# CAN_Interface.net
KiCad netlist of a schematic drawn in Altium Designer
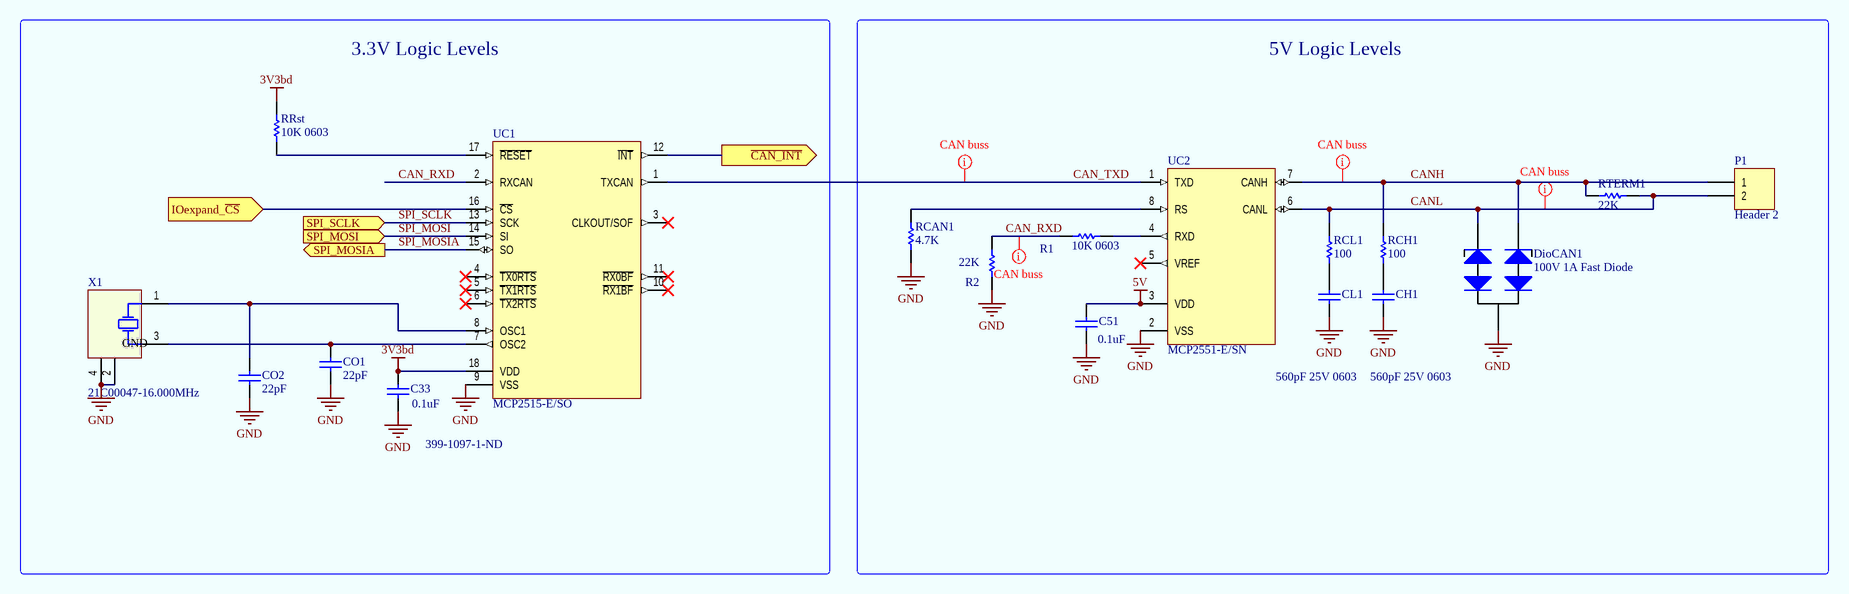
[diagram p0: CAN_Interface.SchDoc]

(export (version "E")
  (design (tool "Eeschema 10.0.6"))
  (components
    (comp (ref "C33")
      (value "0.1uF")
      (footprint "0603C_L")
      (fields
        (field (name "SUPPLIER PART NUMBER 1") "399-1097-1-ND")
        (field (name "MANUFACTURER") "Kemet")
        (field (name "MANUFACTURER PART NUMBER") "C0603C104J4RACTU")
        (field (name "TOLERANCE") "5%")
      )
      (libsource (lib "WCT") (part "Cap10uF_25V_0603"))
    )
    (comp (ref "C51")
      (value "0.1uF")
      (footprint "0603C_L")
      (libsource (lib "ICEdigikey") (part "Cap10uF_25V_0603"))
    )
    (comp (ref "CH1")
      (value "560pF 25V 0603")
      (footprint "0603C_L")
      (fields
        (field (name "MANUFACTURER") "Taiyo Yuden")
        (field (name "MANUFACTURER PART NUMBER") "TMK316F106ZL-T")
        (field (name "TOLERANCE") "-20%, +80%")
      )
      (libsource (lib "WCT") (part "Cap560pF_25V_0603"))
    )
    (comp (ref "CL1")
      (value "560pF 25V 0603")
      (footprint "0603C_L")
      (fields
        (field (name "MANUFACTURER") "Taiyo Yuden")
        (field (name "MANUFACTURER PART NUMBER") "TMK316F106ZL-T")
        (field (name "TOLERANCE") "-20%, +80%")
      )
      (libsource (lib "WCT") (part "Cap560pF_25V_0603"))
    )
    (comp (ref "CO1")
      (value "22pF")
      (footprint "0603C_L")
      (fields
        (field (name "MANUFACTURER") "Murata")
        (field (name "MANUFACTURER PART NUMBER") "GRM1885C1H220JA01D")
        (field (name "TOLERANCE") "5")
      )
      (libsource (lib "WCT") (part "Cap22pF_50V_0603"))
    )
    (comp (ref "CO2")
      (value "22pF")
      (footprint "0603C_L")
      (fields
        (field (name "MANUFACTURER") "Murata")
        (field (name "MANUFACTURER PART NUMBER") "GRM1885C1H220JA01D")
        (field (name "TOLERANCE") "5")
      )
      (libsource (lib "WCT") (part "Cap101nF_50V_0603"))
    )
    (comp (ref "DioCAN1")
      (value "100V 1A Fast Diode")
      (footprint "SOT23")
      (description "High Conductance Fast Diode")
      (fields
        (field (name "MANUFACTURER") "ON Semiconductor")
        (field (name "MANUFACTURER PART NUMBER") "MUR110RLG")
      )
      (libsource (lib "WCT") (part "PESD1CAN"))
    )
    (comp (ref "P1")
      (value "Header 2")
      (footprint "HDR1X2")
      (description "Header, 2-Pin")
      (fields (field (name "PUBLISHER") "Altium Limited"))
      (libsource (lib "Miscellaneous Connectors") (part "Header 2"))
    )
    (comp (ref "R1")
      (value "10K 0603")
      (footprint "0603_L")
      (fields
        (field (name "MANUFACTURER") "Yageo")
        (field (name "MANUFACTURER PART NUMBER") "RT0603DRD074K99L")
        (field (name "TOLERANCE") "±0.5%")
      )
      (libsource (lib "ICEdigikey") (part "Res4K99_0603"))
    )
    (comp (ref "R2")
      (value "22K")
      (footprint "0603_L")
      (fields
        (field (name "MANUFACTURER") "Yageo")
        (field (name "MANUFACTURER PART NUMBER") "RT0603DRD0722KL")
        (field (name "TOLERANCE") "0.5 %")
      )
      (libsource (lib "ICEdigikey") (part "Res_0603"))
    )
    (comp (ref "RCAN1")
      (value "4.7K")
      (footprint "0603_L")
      (fields
        (field (name "MANUFACTURER") "Yageo")
        (field (name "MANUFACTURER PART NUMBER") "RT0603DRD074K99L")
        (field (name "TOLERANCE") "±0.5%")
      )
      (libsource (lib "ICEdigikey") (part "Res4K99_0603"))
    )
    (comp (ref "RCH1")
      (value "100")
      (footprint "0603_L")
      (fields
        (field (name "MANUFACTURER") "Yageo")
        (field (name "MANUFACTURER PART NUMBER") "RC0603JR-07330RL")
        (field (name "TOLERANCE") "±5%")
      )
      (libsource (lib "ICEdigikey") (part "Res330_0603"))
    )
    (comp (ref "RCL1")
      (value "100")
      (footprint "0603_L")
      (fields
        (field (name "MANUFACTURER") "Yageo")
        (field (name "MANUFACTURER PART NUMBER") "RC0603JR-07330RL")
        (field (name "TOLERANCE") "±5%")
      )
      (libsource (lib "ICEdigikey") (part "Res330_0603"))
    )
    (comp (ref "RRst")
      (value "10K 0603")
      (footprint "0603_L")
      (fields
        (field (name "MANUFACTURER") "Panasonic Electronic Components")
        (field (name "MANUFACTURER PART NUMBER") "ERJ-3GEYJ102V")
        (field (name "TOLERANCE") "±5%")
      )
      (libsource (lib "WCT") (part "Res10K_0603"))
    )
    (comp (ref "RTERM1")
      (value "22K")
      (footprint "0603_L")
      (fields
        (field (name "MANUFACTURER") "Yageo")
        (field (name "MANUFACTURER PART NUMBER") "RT0603DRD0722KL")
        (field (name "TOLERANCE") "0.5 %")
      )
      (libsource (lib "WCT") (part "Res_0603"))
    )
    (comp (ref "UC1")
      (value "MCP2515-E/SO")
      (footprint "SOIC-SO18_M")
      (description "Stand-Alone CAN Controller With SPI Interface, 18-Pin SOIC, Extended Temperature")
      (libsource (lib "Altium Content Vault") (part "CMP-0186-00035-2"))
    )
    (comp (ref "UC2")
      (value "MCP2551-E/SN")
      (footprint "SOIC-SN8_N")
      (description "High-Speed CAN Transceiver, 8-Pin SOIC, Extended Temperature")
      (libsource (lib "Altium Content Vault") (part "CMP-0186-00038-2"))
    )
    (comp (ref "X1")
      (value "21C00047-16.000MHz")
      (footprint "ITTI-21C00047-16.000MHz-4_V")
      (description "Crystal, 16 MHz, -30 to 85 degC, 3.2 x 2.5 x 0.9 mm SMD")
      (fields (field (name "MANUFACTURER") "ITTI"))
      (libsource (lib "Altium Content Vault") (part "CMP-0464-00001-2"))
    )
  )
  (nets
    (net (code "1") (name "/CANH") (class "Default")
      (node (ref "DioCAN1") (pin "1") (pinfunction "A_1") (pintype "passive"))
      (node (ref "P1") (pin "1") (pinfunction "1_1") (pintype "passive"))
      (node (ref "RCH1") (pin "2") (pinfunction "2_2") (pintype "passive"))
      (node (ref "RTERM1") (pin "2") (pinfunction "2_2") (pintype "passive"))
      (node (ref "UC2") (pin "7") (pinfunction "CANH_7") (pintype "bidirectional"))
    )
    (net (code "2") (name "/CANL") (class "Default")
      (node (ref "DioCAN1") (pin "2") (pinfunction "K_2") (pintype "passive"))
      (node (ref "P1") (pin "2") (pinfunction "2_2") (pintype "passive"))
      (node (ref "RCL1") (pin "2") (pinfunction "2_2") (pintype "passive"))
      (node (ref "RTERM1") (pin "1") (pinfunction "1_1") (pintype "passive"))
      (node (ref "UC2") (pin "6") (pinfunction "CANL_6") (pintype "bidirectional"))
    )
    (net (code "3") (name "/CAN_INT") (class "Default")
      (node (ref "UC1") (pin "12") (pinfunction "~{INT}_12") (pintype "output"))
    )
    (net (code "4") (name "/CAN_RXD") (class "Default")
      (node (ref "R1") (pin "2") (pinfunction "2_2") (pintype "passive"))
      (node (ref "R2") (pin "2") (pinfunction "2_2") (pintype "passive"))
      (node (ref "UC1") (pin "2") (pinfunction "RXCAN_2") (pintype "input"))
    )
    (net (code "5") (name "/CAN_TXD") (class "Default")
      (node (ref "UC1") (pin "1") (pinfunction "TXCAN_1") (pintype "output"))
      (node (ref "UC2") (pin "1") (pinfunction "TXD_1") (pintype "input"))
    )
    (net (code "6") (name "/IOexpand_~{CS}") (class "Default")
      (node (ref "UC1") (pin "16") (pinfunction "~{CS}_16") (pintype "input"))
    )
    (net (code "7") (name "/SPI_MOSI") (class "Default")
      (node (ref "UC1") (pin "14") (pinfunction "SI_14") (pintype "input"))
    )
    (net (code "8") (name "/SPI_MOSIA") (class "Default")
      (node (ref "UC1") (pin "15") (pinfunction "SO_15") (pintype "bidirectional"))
    )
    (net (code "9") (name "/SPI_SCLK") (class "Default")
      (node (ref "UC1") (pin "13") (pinfunction "SCK_13") (pintype "input"))
    )
    (net (code "10") (name "3V3bd") (class "Default")
      (node (ref "C33") (pin "2") (pinfunction "2_2") (pintype "passive"))
      (node (ref "RRst") (pin "2") (pinfunction "2_2") (pintype "passive"))
      (node (ref "UC1") (pin "18") (pinfunction "VDD_18") (pintype "power_in"))
    )
    (net (code "11") (name "5V") (class "Default")
      (node (ref "C51") (pin "2") (pinfunction "2_2") (pintype "passive"))
      (node (ref "UC2") (pin "3") (pinfunction "VDD_3") (pintype "power_in"))
    )
    (net (code "12") (name "GND") (class "Default")
      (node (ref "C33") (pin "1") (pinfunction "1_1") (pintype "passive"))
      (node (ref "C51") (pin "1") (pinfunction "1_1") (pintype "passive"))
      (node (ref "CH1") (pin "2") (pinfunction "2_2") (pintype "passive"))
      (node (ref "CL1") (pin "1") (pinfunction "1_1") (pintype "passive"))
      (node (ref "CO1") (pin "1") (pinfunction "1_1") (pintype "passive"))
      (node (ref "CO2") (pin "2") (pinfunction "2_2") (pintype "passive"))
      (node (ref "DioCAN1") (pin "3") (pinfunction "3_3") (pintype "passive"))
      (node (ref "R2") (pin "1") (pinfunction "1_1") (pintype "passive"))
      (node (ref "RCAN1") (pin "1") (pinfunction "1_1") (pintype "passive"))
      (node (ref "UC1") (pin "9") (pinfunction "VSS_9") (pintype "power_in"))
      (node (ref "UC2") (pin "2") (pinfunction "VSS_2") (pintype "power_in"))
      (node (ref "X1") (pin "2") (pinfunction "GND_2") (pintype "power_in"))
      (node (ref "X1") (pin "4") (pinfunction "GND_4") (pintype "power_in"))
    )
    (net (code "13") (name "Net-(CH1-Pad1)") (class "Default")
      (node (ref "CH1") (pin "1") (pinfunction "1_1") (pintype "passive"))
      (node (ref "RCH1") (pin "1") (pinfunction "1_1") (pintype "passive"))
    )
    (net (code "14") (name "Net-(CL1-Pad2)") (class "Default")
      (node (ref "CL1") (pin "2") (pinfunction "2_2") (pintype "passive"))
      (node (ref "RCL1") (pin "1") (pinfunction "1_1") (pintype "passive"))
    )
    (net (code "15") (name "Net-(UC1-OSC1)") (class "Default")
      (node (ref "CO2") (pin "1") (pinfunction "1_1") (pintype "passive"))
      (node (ref "UC1") (pin "8") (pinfunction "OSC1_8") (pintype "input"))
      (node (ref "X1") (pin "1") (pinfunction "XTAL_1") (pintype "passive"))
    )
    (net (code "16") (name "Net-(UC1-OSC2)") (class "Default")
      (node (ref "CO1") (pin "2") (pinfunction "2_2") (pintype "passive"))
      (node (ref "UC1") (pin "7") (pinfunction "OSC2_7") (pintype "output"))
      (node (ref "X1") (pin "3") (pinfunction "XTAL_3") (pintype "passive"))
    )
    (net (code "17") (name "Net-(UC1-~{RESET})") (class "Default")
      (node (ref "RRst") (pin "1") (pinfunction "1_1") (pintype "passive"))
      (node (ref "UC1") (pin "17") (pinfunction "~{RESET}_17") (pintype "input"))
    )
    (net (code "18") (name "Net-(UC2-RS)") (class "Default")
      (node (ref "RCAN1") (pin "2") (pinfunction "2_2") (pintype "passive"))
      (node (ref "UC2") (pin "8") (pinfunction "RS_8") (pintype "input"))
    )
    (net (code "19") (name "Net-(UC2-RXD)") (class "Default")
      (node (ref "R1") (pin "1") (pinfunction "1_1") (pintype "passive"))
      (node (ref "UC2") (pin "4") (pinfunction "RXD_4") (pintype "output"))
    )
    (net (code "20") (name "unconnected-(UC1-CLKOUT{slash}SOF-Pad3)") (class "Default")
      (node (ref "UC1") (pin "3") (pinfunction "CLKOUT/SOF_3") (pintype "output+no_connect"))
    )
    (net (code "21") (name "unconnected-(UC1-~{RX0BF}-Pad11)") (class "Default")
      (node (ref "UC1") (pin "11") (pinfunction "~{RX0BF}_11") (pintype "output+no_connect"))
    )
    (net (code "22") (name "unconnected-(UC1-~{RX1BF}-Pad10)") (class "Default")
      (node (ref "UC1") (pin "10") (pinfunction "~{RX1BF}_10") (pintype "output+no_connect"))
    )
    (net (code "23") (name "unconnected-(UC1-~{TX0RTS}-Pad4)") (class "Default")
      (node (ref "UC1") (pin "4") (pinfunction "~{TX0RTS}_4") (pintype "input+no_connect"))
    )
    (net (code "24") (name "unconnected-(UC1-~{TX1RTS}-Pad5)") (class "Default")
      (node (ref "UC1") (pin "5") (pinfunction "~{TX1RTS}_5") (pintype "input+no_connect"))
    )
    (net (code "25") (name "unconnected-(UC1-~{TX2RTS}-Pad6)") (class "Default")
      (node (ref "UC1") (pin "6") (pinfunction "~{TX2RTS}_6") (pintype "input+no_connect"))
    )
    (net (code "26") (name "unconnected-(UC2-VREF-Pad5)") (class "Default")
      (node (ref "UC2") (pin "5") (pinfunction "VREF_5") (pintype "output+no_connect"))
    )
  )
)
